# MCUHighSpeed.net
KiCad netlist of a schematic drawn in Altium Designer
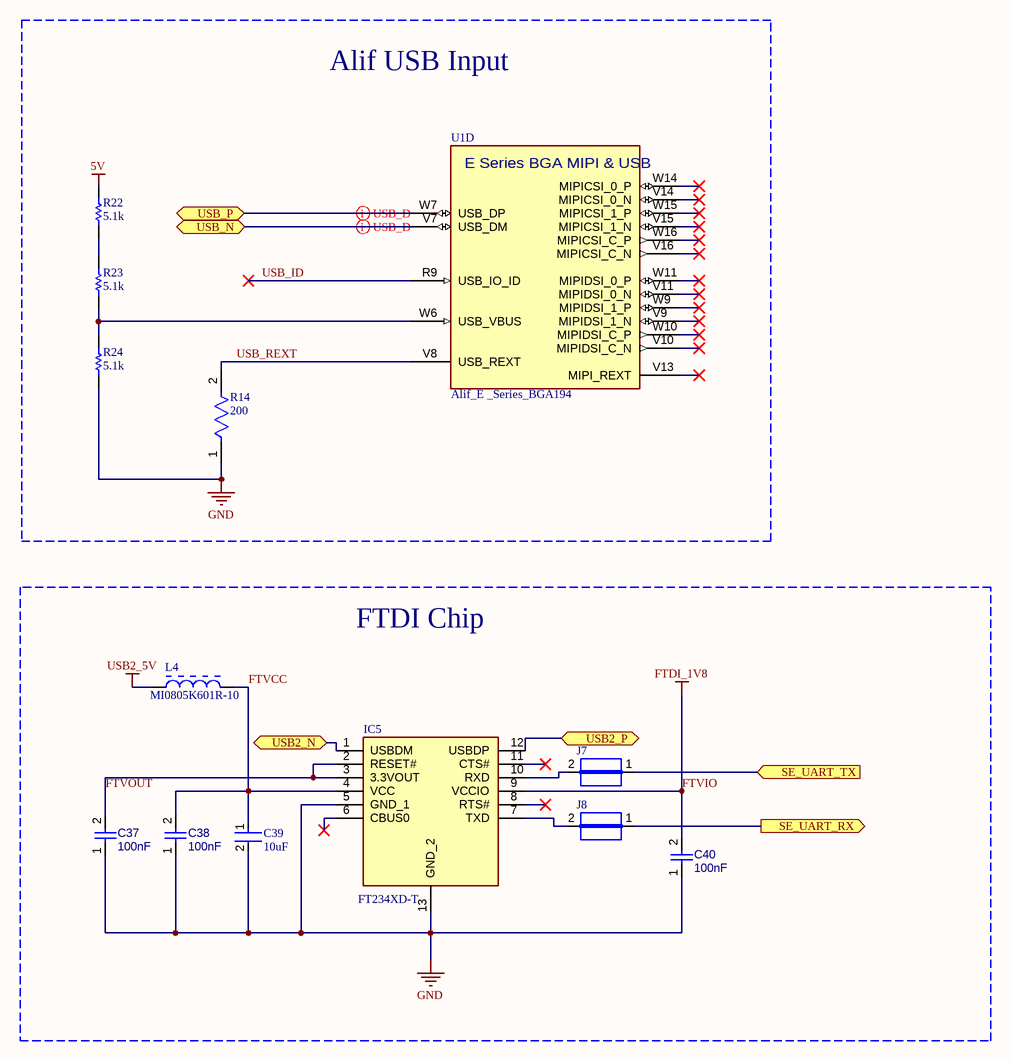
[diagram p0: MCUHighSpeed.SchDoc]

(export (version "E")
  (design (tool "Eeschema 10.0.6"))
  (components
    (comp (ref "C37")
      (value "100nF")
      (footprint "FP-C0603X104K3RACTU-IPC_C")
      (libsource (lib "Gustav Eckerbom") (part "CAP-NP-2"))
    )
    (comp (ref "C38")
      (value "100nF")
      (footprint "FP-C0603X104K3RACTU-IPC_C")
      (libsource (lib "Gustav Eckerbom") (part "CAP-NP-2"))
    )
    (comp (ref "C39")
      (value "10uF")
      (footprint "FP-CC0603-0_15-0_95-IPC_C")
      (libsource (lib "Gustav Eckerbom") (part "02cd4be3c70576c341d710602a673aa"))
    )
    (comp (ref "C40")
      (value "100nF")
      (footprint "FP-C0603X104K3RACTU-IPC_C")
      (libsource (lib "Gustav Eckerbom") (part "CAP-NP-2"))
    )
    (comp (ref "IC5")
      (value "FT234XD-T")
      (footprint "SamacSys:SON45P300X300X80-13N-D")
      (description "Integrated Circuit")
      (libsource (lib "*") (part "FT234XD-T"))
    )
    (comp (ref "J7")
      (value "JUMPER")
      (footprint "JUMPER")
      (libsource (lib "Gustav Eckerbom") (part "JUMPER"))
    )
    (comp (ref "J8")
      (value "JUMPER")
      (footprint "JUMPER")
      (libsource (lib "Gustav Eckerbom") (part "JUMPER"))
    )
    (comp (ref "L4")
      (value "MI0805K601R-10")
      (footprint "LIRD-MI0805K601R-10-2_V")
      (fields (field (name "MANUFACTURER") "Laird"))
      (libsource (lib "Altium Content Vault") (part "IND-FB-2"))
    )
    (comp (ref "R14")
      (value "200")
      (footprint "FP-MCR03-IPC_C")
      (fields (field (name "POWER") "100mW") (field (name "TOLERANCE") "5%") (field (name "Comment") "200R"))
      (libsource (lib "Gustav Eckerbom") (part "1029c3af85768c4190bb7ad29bc67b5"))
    )
    (comp (ref "R22")
      (value "5.1k")
      (footprint "RESC1608X55X30LL15T15")
      (fields (field (name "PART NUMBER") "ERJ-3GEYJ512V") (field (name "MANUFACTURER") "Panasonic"))
      (libsource (lib "Altium Content Vault") (part "RES"))
    )
    (comp (ref "R23")
      (value "5.1k")
      (footprint "RESC1608X55X30LL15T15")
      (fields (field (name "PART NUMBER") "ERJ-3GEYJ512V") (field (name "MANUFACTURER") "Panasonic"))
      (libsource (lib "Altium Content Vault") (part "RES"))
    )
    (comp (ref "R24")
      (value "5.1k")
      (footprint "RESC1608X55X30LL15T15")
      (fields (field (name "PART NUMBER") "ERJ-3GEYJ512V") (field (name "MANUFACTURER") "Panasonic"))
      (libsource (lib "Altium Content Vault") (part "RES"))
    )
    (comp (ref "U1")
      (value "Alif_E _Series_BGA194")
      (footprint "BGA194 _CENTERED")
      (description "IC,Alif E7 MCU, Rev B silicon,BGA194")
      (libsource (lib "AlifSoC") (part "E7_B0_194BGA"))
    )
  )
  (nets
    (net (code "1") (name "/FTVCC") (class "Default")
      (node (ref "C38") (pin "2") (pinfunction "2_2") (pintype "passive"))
      (node (ref "C39") (pin "1") (pinfunction "1_1") (pintype "passive"))
      (node (ref "IC5") (pin "4") (pinfunction "VCC_4") (pintype "passive"))
      (node (ref "L4") (pin "2") (pinfunction "2_2") (pintype "passive"))
    )
    (net (code "2") (name "/FTVOUT") (class "Default")
      (node (ref "C37") (pin "2") (pinfunction "2_2") (pintype "passive"))
      (node (ref "IC5") (pin "2") (pinfunction "RESET#_2") (pintype "passive"))
      (node (ref "IC5") (pin "3") (pinfunction "3.3VOUT_3") (pintype "passive"))
    )
    (net (code "3") (name "/SE_UART_RX") (class "Default")
      (node (ref "J8") (pin "1") (pinfunction "1_1") (pintype "passive"))
    )
    (net (code "4") (name "/SE_UART_TX") (class "Default")
      (node (ref "J7") (pin "1") (pinfunction "1_1") (pintype "passive"))
    )
    (net (code "5") (name "/USB2_N") (class "Default")
      (node (ref "IC5") (pin "1") (pinfunction "USBDM_1") (pintype "passive"))
    )
    (net (code "6") (name "/USB2_P") (class "Default")
      (node (ref "IC5") (pin "12") (pinfunction "USBDP_12") (pintype "passive"))
    )
    (net (code "7") (name "/USB_ID") (class "Default")
      (node (ref "U1") (pin "R9") (pinfunction "USB_IO_ID_R9") (pintype "input+no_connect"))
    )
    (net (code "8") (name "/USB_N") (class "Default")
      (node (ref "U1") (pin "V7") (pinfunction "USB_DM_V7") (pintype "bidirectional"))
    )
    (net (code "9") (name "/USB_P") (class "Default")
      (node (ref "U1") (pin "W7") (pinfunction "USB_DP_W7") (pintype "bidirectional"))
    )
    (net (code "10") (name "/USB_REXT") (class "Default")
      (node (ref "R14") (pin "2") (pinfunction "2_2") (pintype "passive"))
      (node (ref "U1") (pin "V8") (pinfunction "USB_REXT_V8") (pintype "passive"))
    )
    (net (code "11") (name "5V") (class "Default")
      (node (ref "R22") (pin "2") (pinfunction "2_2") (pintype "passive"))
    )
    (net (code "12") (name "FTDI_1V8") (class "Default")
      (node (ref "C40") (pin "2") (pinfunction "2_2") (pintype "passive"))
      (node (ref "IC5") (pin "9") (pinfunction "VCCIO_9") (pintype "passive"))
    )
    (net (code "13") (name "GND") (class "Default")
      (node (ref "C37") (pin "1") (pinfunction "1_1") (pintype "passive"))
      (node (ref "C38") (pin "1") (pinfunction "1_1") (pintype "passive"))
      (node (ref "C39") (pin "2") (pinfunction "2_2") (pintype "passive"))
      (node (ref "C40") (pin "1") (pinfunction "1_1") (pintype "passive"))
      (node (ref "IC5") (pin "13") (pinfunction "GND_2_13") (pintype "passive"))
      (node (ref "IC5") (pin "5") (pinfunction "GND_1_5") (pintype "passive"))
      (node (ref "R14") (pin "1") (pinfunction "1_1") (pintype "passive"))
      (node (ref "R24") (pin "1") (pinfunction "1_1") (pintype "passive"))
    )
    (net (code "14") (name "Net-(IC5-RXD)") (class "Default")
      (node (ref "IC5") (pin "10") (pinfunction "RXD_10") (pintype "passive"))
      (node (ref "J7") (pin "2") (pinfunction "2_2") (pintype "passive"))
    )
    (net (code "15") (name "Net-(IC5-TXD)") (class "Default")
      (node (ref "IC5") (pin "7") (pinfunction "TXD_7") (pintype "passive"))
      (node (ref "J8") (pin "2") (pinfunction "2_2") (pintype "passive"))
    )
    (net (code "16") (name "Net-(R22-Pad1)") (class "Default")
      (node (ref "R22") (pin "1") (pinfunction "1_1") (pintype "passive"))
      (node (ref "R23") (pin "2") (pinfunction "2_2") (pintype "passive"))
    )
    (net (code "17") (name "Net-(U1D-USB_VBUS)") (class "Default")
      (node (ref "R23") (pin "1") (pinfunction "1_1") (pintype "passive"))
      (node (ref "R24") (pin "2") (pinfunction "2_2") (pintype "passive"))
      (node (ref "U1") (pin "W6") (pinfunction "USB_VBUS_W6") (pintype "input"))
    )
    (net (code "18") (name "USB2_5V") (class "Default")
      (node (ref "L4") (pin "1") (pinfunction "1_1") (pintype "passive"))
    )
    (net (code "19") (name "unconnected-(IC5-CBUS0-Pad6)") (class "Default")
      (node (ref "IC5") (pin "6") (pinfunction "CBUS0_6") (pintype "passive+no_connect"))
    )
    (net (code "20") (name "unconnected-(IC5-CTS#-Pad11)") (class "Default")
      (node (ref "IC5") (pin "11") (pinfunction "CTS#_11") (pintype "passive+no_connect"))
    )
    (net (code "21") (name "unconnected-(IC5-RTS#-Pad8)") (class "Default")
      (node (ref "IC5") (pin "8") (pinfunction "RTS#_8") (pintype "passive+no_connect"))
    )
    (net (code "22") (name "unconnected-(U1D-MIPICSI_0_N-PadV14)") (class "Default")
      (node (ref "U1") (pin "V14") (pinfunction "MIPICSI_0_N_V14") (pintype "bidirectional+no_connect"))
    )
    (net (code "23") (name "unconnected-(U1D-MIPICSI_0_P-PadW14)") (class "Default")
      (node (ref "U1") (pin "W14") (pinfunction "MIPICSI_0_P_W14") (pintype "bidirectional+no_connect"))
    )
    (net (code "24") (name "unconnected-(U1D-MIPICSI_1_N-PadV15)") (class "Default")
      (node (ref "U1") (pin "V15") (pinfunction "MIPICSI_1_N_V15") (pintype "bidirectional+no_connect"))
    )
    (net (code "25") (name "unconnected-(U1D-MIPICSI_1_P-PadW15)") (class "Default")
      (node (ref "U1") (pin "W15") (pinfunction "MIPICSI_1_P_W15") (pintype "bidirectional+no_connect"))
    )
    (net (code "26") (name "unconnected-(U1D-MIPICSI_C_N-PadV16)") (class "Default")
      (node (ref "U1") (pin "V16") (pinfunction "MIPICSI_C_N_V16") (pintype "output+no_connect"))
    )
    (net (code "27") (name "unconnected-(U1D-MIPICSI_C_P-PadW16)") (class "Default")
      (node (ref "U1") (pin "W16") (pinfunction "MIPICSI_C_P_W16") (pintype "output+no_connect"))
    )
    (net (code "28") (name "unconnected-(U1D-MIPIDSI_0_N-PadV11)") (class "Default")
      (node (ref "U1") (pin "V11") (pinfunction "MIPIDSI_0_N_V11") (pintype "bidirectional+no_connect"))
    )
    (net (code "29") (name "unconnected-(U1D-MIPIDSI_0_P-PadW11)") (class "Default")
      (node (ref "U1") (pin "W11") (pinfunction "MIPIDSI_0_P_W11") (pintype "bidirectional+no_connect"))
    )
    (net (code "30") (name "unconnected-(U1D-MIPIDSI_1_N-PadV9)") (class "Default")
      (node (ref "U1") (pin "V9") (pinfunction "MIPIDSI_1_N_V9") (pintype "bidirectional+no_connect"))
    )
    (net (code "31") (name "unconnected-(U1D-MIPIDSI_1_P-PadW9)") (class "Default")
      (node (ref "U1") (pin "W9") (pinfunction "MIPIDSI_1_P_W9") (pintype "bidirectional+no_connect"))
    )
    (net (code "32") (name "unconnected-(U1D-MIPIDSI_C_N-PadV10)") (class "Default")
      (node (ref "U1") (pin "V10") (pinfunction "MIPIDSI_C_N_V10") (pintype "output+no_connect"))
    )
    (net (code "33") (name "unconnected-(U1D-MIPIDSI_C_P-PadW10)") (class "Default")
      (node (ref "U1") (pin "W10") (pinfunction "MIPIDSI_C_P_W10") (pintype "output+no_connect"))
    )
    (net (code "34") (name "unconnected-(U1D-MIPI_REXT-PadV13)") (class "Default")
      (node (ref "U1") (pin "V13") (pinfunction "MIPI_REXT_V13") (pintype "passive+no_connect"))
    )
  )
)
